# LED_Schematic_Final.net
KiCad netlist of a schematic drawn in EAGLE
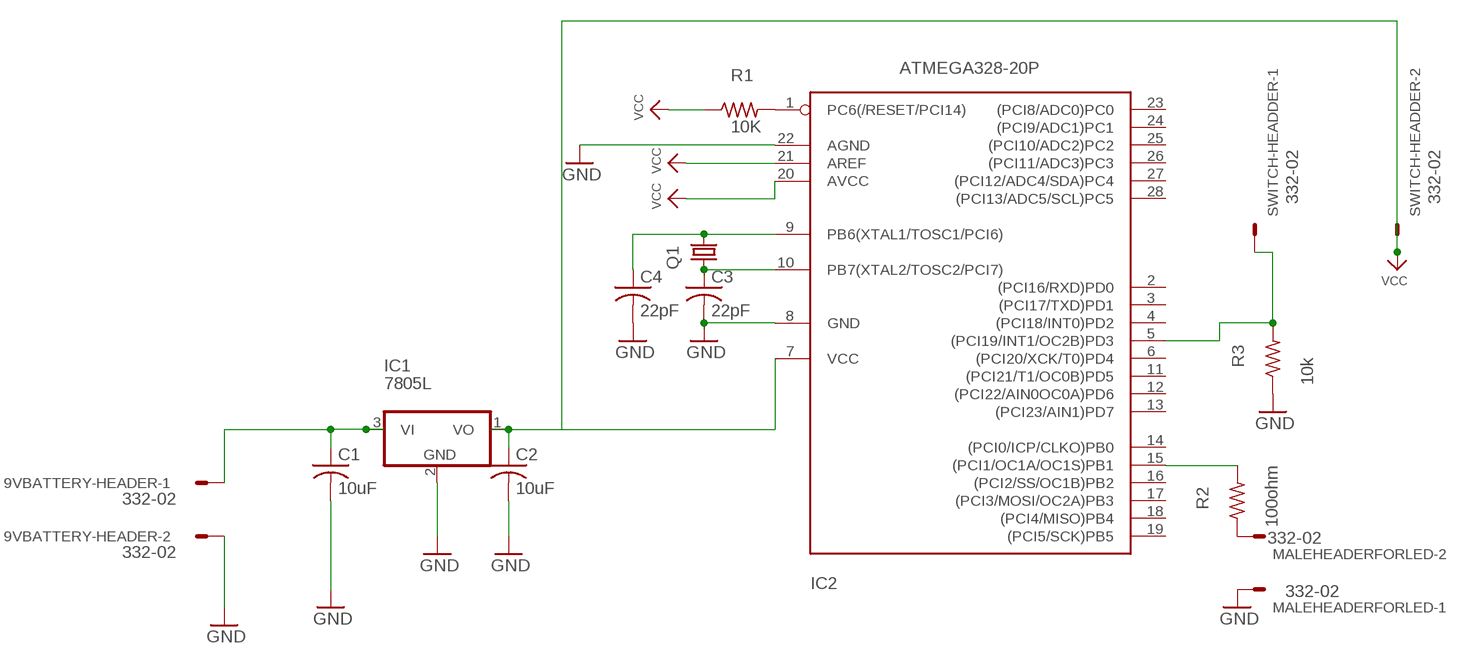
[diagram p0: schematic, sheet 1]

(export (version "E")
  (design (tool "Eeschema 10.0.6"))
  (components
    (comp (ref "9VBATTERY-HEADER")
      (value "332-02")
      (footprint "eagle-import:332-02")
      (libsource (lib "eagle-import") (part "332-02"))
    )
    (comp (ref "C1")
      (value "10uF")
      (footprint "eagle-import:C025-040X050")
      (libsource (lib "eagle-import") (part "C-US025-040X050"))
    )
    (comp (ref "C2")
      (value "10uF")
      (footprint "eagle-import:C025-040X050")
      (libsource (lib "eagle-import") (part "C-US025-040X050"))
    )
    (comp (ref "C3")
      (value "22pF")
      (footprint "eagle-import:C025-040X050")
      (libsource (lib "eagle-import") (part "C-US025-040X050"))
    )
    (comp (ref "C4")
      (value "22pF")
      (footprint "eagle-import:C025-040X050")
      (libsource (lib "eagle-import") (part "C-US025-040X050"))
    )
    (comp (ref "IC1")
      (value "7805L")
      (footprint "eagle-import:TO92")
      (libsource (lib "eagle-import") (part "78L05"))
    )
    (comp (ref "IC2")
      (value "ATMEGA328-20P")
      (footprint "eagle-import:DIL28-3")
      (libsource (lib "eagle-import") (part "ATMEGA328P-20"))
    )
    (comp (ref "MALEHEADERFORLED")
      (value "332-02")
      (footprint "eagle-import:332-02")
      (libsource (lib "eagle-import") (part "332-02"))
    )
    (comp (ref "Q1")
      (value "CRYSTALHC49S")
      (footprint "eagle-import:HC49_S")
      (libsource (lib "eagle-import") (part "CRYSTALHC49S"))
    )
    (comp (ref "R1")
      (value "10K")
      (footprint "eagle-import:0207_12")
      (libsource (lib "eagle-import") (part "R-US_0207/12"))
    )
    (comp (ref "R2")
      (value "100ohm")
      (footprint "eagle-import:0207_12")
      (libsource (lib "eagle-import") (part "R-US_0207/12"))
    )
    (comp (ref "R3")
      (value "10k")
      (footprint "eagle-import:0207_12")
      (fields (field (name "SPICEPREFIX") "R"))
      (libsource (lib "eagle-import") (part "R-US_0207/12"))
    )
    (comp (ref "SWITCH-HEADDER")
      (value "332-02")
      (footprint "eagle-import:332-02")
      (libsource (lib "eagle-import") (part "332-02"))
    )
  )
  (nets
    (net (code "1") (name "GND") (class "Default")
      (node (ref "9VBATTERY-HEADER") (pin "2") (pinfunction "S_2") (pintype "passive"))
      (node (ref "C1") (pin "2") (pinfunction "2_2") (pintype "passive"))
      (node (ref "C2") (pin "2") (pinfunction "2_2") (pintype "passive"))
      (node (ref "C3") (pin "2") (pinfunction "2_2") (pintype "passive"))
      (node (ref "C4") (pin "2") (pinfunction "2_2") (pintype "passive"))
      (node (ref "IC1") (pin "2") (pinfunction "GND_2") (pintype "passive"))
      (node (ref "IC2") (pin "22") (pinfunction "AGND_22") (pintype "bidirectional"))
      (node (ref "IC2") (pin "8") (pinfunction "GND_8") (pintype "bidirectional"))
      (node (ref "MALEHEADERFORLED") (pin "1") (pinfunction "S_1") (pintype "passive"))
      (node (ref "R3") (pin "1") (pinfunction "1_1") (pintype "passive"))
    )
    (net (code "2") (name "Net-(9VBATTERY-HEADERA-S)") (class "Default")
      (node (ref "9VBATTERY-HEADER") (pin "1") (pinfunction "S_1") (pintype "passive"))
      (node (ref "C1") (pin "1") (pinfunction "1_1") (pintype "passive"))
      (node (ref "IC1") (pin "3") (pinfunction "VI_3") (pintype "input"))
    )
    (net (code "3") (name "Net-(IC2-(PCI1{slash}OC1A{slash}OC1S)PB1)") (class "Default")
      (node (ref "IC2") (pin "15") (pinfunction "(PCI1/OC1A/OC1S)PB1_15") (pintype "bidirectional"))
      (node (ref "R2") (pin "2") (pinfunction "2_2") (pintype "passive"))
    )
    (net (code "4") (name "Net-(IC2-(PCI19{slash}INT1{slash}OC2B)PD3)") (class "Default")
      (node (ref "IC2") (pin "5") (pinfunction "(PCI19/INT1/OC2B)PD3_5") (pintype "bidirectional"))
      (node (ref "R3") (pin "2") (pinfunction "2_2") (pintype "passive"))
      (node (ref "SWITCH-HEADDER") (pin "1") (pinfunction "S_1") (pintype "passive"))
    )
    (net (code "5") (name "Net-(IC2-PB6(XTAL1{slash}TOSC1{slash}PCI6))") (class "Default")
      (node (ref "C4") (pin "1") (pinfunction "1_1") (pintype "passive"))
      (node (ref "IC2") (pin "9") (pinfunction "PB6(XTAL1/TOSC1/PCI6)_9") (pintype "bidirectional"))
      (node (ref "Q1") (pin "2") (pinfunction "2_2") (pintype "passive"))
    )
    (net (code "6") (name "Net-(IC2-PB7(XTAL2{slash}TOSC2{slash}PCI7))") (class "Default")
      (node (ref "C3") (pin "1") (pinfunction "1_1") (pintype "passive"))
      (node (ref "IC2") (pin "10") (pinfunction "PB7(XTAL2/TOSC2/PCI7)_10") (pintype "bidirectional"))
      (node (ref "Q1") (pin "1") (pinfunction "1_1") (pintype "passive"))
    )
    (net (code "7") (name "Net-(IC2-PC6({slash}RESET{slash}PCI14))") (class "Default")
      (node (ref "IC2") (pin "1") (pinfunction "PC6(/RESET/PCI14)_1") (pintype "bidirectional"))
      (node (ref "R1") (pin "2") (pinfunction "2_2") (pintype "passive"))
    )
    (net (code "8") (name "Net-(MALEHEADERFORLEDB-S)") (class "Default")
      (node (ref "MALEHEADERFORLED") (pin "2") (pinfunction "S_2") (pintype "passive"))
      (node (ref "R2") (pin "1") (pinfunction "1_1") (pintype "passive"))
    )
    (net (code "9") (name "VCC") (class "Default")
      (node (ref "C2") (pin "1") (pinfunction "1_1") (pintype "passive"))
      (node (ref "IC1") (pin "1") (pinfunction "VO_1") (pintype "passive"))
      (node (ref "IC2") (pin "20") (pinfunction "AVCC_20") (pintype "bidirectional"))
      (node (ref "IC2") (pin "21") (pinfunction "AREF_21") (pintype "bidirectional"))
      (node (ref "IC2") (pin "7") (pinfunction "VCC_7") (pintype "bidirectional"))
      (node (ref "R1") (pin "1") (pinfunction "1_1") (pintype "passive"))
      (node (ref "SWITCH-HEADDER") (pin "2") (pinfunction "S_2") (pintype "passive"))
    )
    (net (code "10") (name "unconnected-(IC2-(PCI0{slash}ICP{slash}CLKO)PB0-Pad14)") (class "Default")
      (node (ref "IC2") (pin "14") (pinfunction "(PCI0/ICP/CLKO)PB0_14") (pintype "bidirectional"))
    )
    (net (code "11") (name "unconnected-(IC2-(PCI2{slash}SS{slash}OC1B)PB2-Pad16)") (class "Default")
      (node (ref "IC2") (pin "16") (pinfunction "(PCI2/SS/OC1B)PB2_16") (pintype "bidirectional"))
    )
    (net (code "12") (name "unconnected-(IC2-(PCI3{slash}MOSI{slash}OC2A)PB3-Pad17)") (class "Default")
      (node (ref "IC2") (pin "17") (pinfunction "(PCI3/MOSI/OC2A)PB3_17") (pintype "bidirectional"))
    )
    (net (code "13") (name "unconnected-(IC2-(PCI4{slash}MISO)PB4-Pad18)") (class "Default")
      (node (ref "IC2") (pin "18") (pinfunction "(PCI4/MISO)PB4_18") (pintype "bidirectional"))
    )
    (net (code "14") (name "unconnected-(IC2-(PCI5{slash}SCK)PB5-Pad19)") (class "Default")
      (node (ref "IC2") (pin "19") (pinfunction "(PCI5/SCK)PB5_19") (pintype "bidirectional"))
    )
    (net (code "15") (name "unconnected-(IC2-(PCI8{slash}ADC0)PC0-Pad23)") (class "Default")
      (node (ref "IC2") (pin "23") (pinfunction "(PCI8/ADC0)PC0_23") (pintype "bidirectional"))
    )
    (net (code "16") (name "unconnected-(IC2-(PCI9{slash}ADC1)PC1-Pad24)") (class "Default")
      (node (ref "IC2") (pin "24") (pinfunction "(PCI9/ADC1)PC1_24") (pintype "bidirectional"))
    )
    (net (code "17") (name "unconnected-(IC2-(PCI10{slash}ADC2)PC2-Pad25)") (class "Default")
      (node (ref "IC2") (pin "25") (pinfunction "(PCI10/ADC2)PC2_25") (pintype "bidirectional"))
    )
    (net (code "18") (name "unconnected-(IC2-(PCI11{slash}ADC3)PC3-Pad26)") (class "Default")
      (node (ref "IC2") (pin "26") (pinfunction "(PCI11/ADC3)PC3_26") (pintype "bidirectional"))
    )
    (net (code "19") (name "unconnected-(IC2-(PCI12{slash}ADC4{slash}SDA)PC4-Pad27)") (class "Default")
      (node (ref "IC2") (pin "27") (pinfunction "(PCI12/ADC4/SDA)PC4_27") (pintype "bidirectional"))
    )
    (net (code "20") (name "unconnected-(IC2-(PCI13{slash}ADC5{slash}SCL)PC5-Pad28)") (class "Default")
      (node (ref "IC2") (pin "28") (pinfunction "(PCI13/ADC5/SCL)PC5_28") (pintype "bidirectional"))
    )
    (net (code "21") (name "unconnected-(IC2-(PCI16{slash}RXD)PD0-Pad2)") (class "Default")
      (node (ref "IC2") (pin "2") (pinfunction "(PCI16/RXD)PD0_2") (pintype "bidirectional"))
    )
    (net (code "22") (name "unconnected-(IC2-(PCI17{slash}TXD)PD1-Pad3)") (class "Default")
      (node (ref "IC2") (pin "3") (pinfunction "(PCI17/TXD)PD1_3") (pintype "bidirectional"))
    )
    (net (code "23") (name "unconnected-(IC2-(PCI18{slash}INT0)PD2-Pad4)") (class "Default")
      (node (ref "IC2") (pin "4") (pinfunction "(PCI18/INT0)PD2_4") (pintype "bidirectional"))
    )
    (net (code "24") (name "unconnected-(IC2-(PCI20{slash}XCK{slash}T0)PD4-Pad6)") (class "Default")
      (node (ref "IC2") (pin "6") (pinfunction "(PCI20/XCK/T0)PD4_6") (pintype "bidirectional"))
    )
    (net (code "25") (name "unconnected-(IC2-(PCI21{slash}T1{slash}OC0B)PD5-Pad11)") (class "Default")
      (node (ref "IC2") (pin "11") (pinfunction "(PCI21/T1/OC0B)PD5_11") (pintype "bidirectional"))
    )
    (net (code "26") (name "unconnected-(IC2-(PCI22{slash}AIN0OC0A)PD6-Pad12)") (class "Default")
      (node (ref "IC2") (pin "12") (pinfunction "(PCI22/AIN0OC0A)PD6_12") (pintype "bidirectional"))
    )
    (net (code "27") (name "unconnected-(IC2-(PCI23{slash}AIN1)PD7-Pad13)") (class "Default")
      (node (ref "IC2") (pin "13") (pinfunction "(PCI23/AIN1)PD7_13") (pintype "bidirectional"))
    )
  )
)
